# JTAG_Trace.net
KiCad netlist of a schematic drawn in Altium Designer
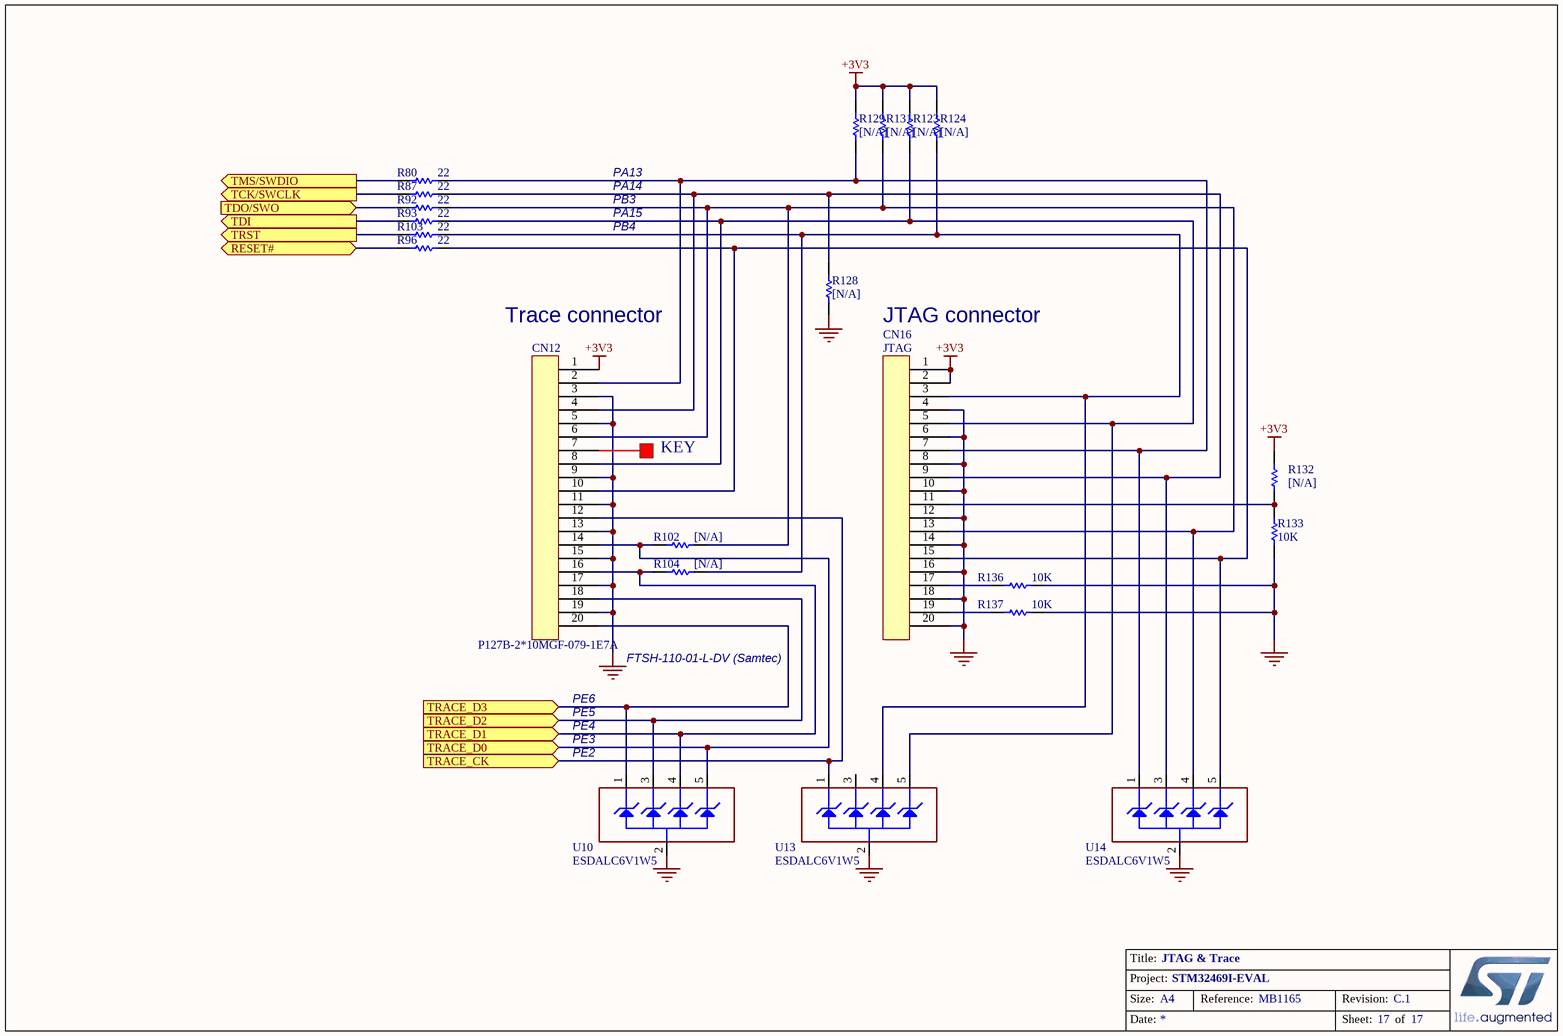
[diagram p0: JTAG&Trace.SchDoc]

(export (version "E")
  (design (tool "Eeschema 10.0.6"))
  (components
    (comp (ref "CN12")
      (value "P127B-2*10MGF-079-1E7A")
      (footprint "FTSH-110-01-L-DV")
      (libsource (lib "*") (part "20PIN1"))
    )
    (comp (ref "CN16") (value "JTAG") (footprint "IDC20S") (libsource (lib "*") (part "20PIN1")))
    (comp (ref "R80")
      (value "22")
      (footprint "0603R")
      (description "Resistor")
      (fields (field (name "PUBLISHER") "Altium Limited"))
      (libsource (lib "Miscellaneous Devices") (part "Res1"))
    )
    (comp (ref "R87")
      (value "22")
      (footprint "0603R")
      (description "Resistor")
      (fields (field (name "PUBLISHER") "Altium Limited"))
      (libsource (lib "Miscellaneous Devices") (part "Res1"))
    )
    (comp (ref "R92")
      (value "22")
      (footprint "0603R")
      (description "Resistor")
      (fields (field (name "PUBLISHER") "Altium Limited"))
      (libsource (lib "Miscellaneous Devices") (part "Res1"))
    )
    (comp (ref "R93")
      (value "22")
      (footprint "0603R")
      (description "Resistor")
      (fields (field (name "PUBLISHER") "Altium Limited"))
      (libsource (lib "Miscellaneous Devices") (part "Res1"))
    )
    (comp (ref "R96")
      (value "22")
      (footprint "0603R")
      (description "Resistor")
      (fields (field (name "PUBLISHER") "Altium Limited"))
      (libsource (lib "Miscellaneous Devices") (part "Res1"))
    )
    (comp (ref "R102")
      (value "[N/A]")
      (footprint "0603R")
      (description "Resistor")
      (fields (field (name "PUBLISHER") "Altium Limited"))
      (libsource (lib "Miscellaneous Devices") (part "Res1"))
    )
    (comp (ref "R103")
      (value "22")
      (footprint "0603R")
      (description "Resistor")
      (fields (field (name "PUBLISHER") "Altium Limited"))
      (libsource (lib "Miscellaneous Devices") (part "Res1"))
    )
    (comp (ref "R104")
      (value "[N/A]")
      (footprint "0603R")
      (description "Resistor")
      (fields (field (name "PUBLISHER") "Altium Limited"))
      (libsource (lib "Miscellaneous Devices") (part "Res1"))
    )
    (comp (ref "R123")
      (value "[N/A]")
      (footprint "0603R")
      (description "Resistor")
      (fields (field (name "PUBLISHER") "Altium Limited"))
      (libsource (lib "Miscellaneous Devices") (part "Res1"))
    )
    (comp (ref "R124")
      (value "[N/A]")
      (footprint "0603R")
      (description "Resistor")
      (fields (field (name "PUBLISHER") "Altium Limited"))
      (libsource (lib "Miscellaneous Devices") (part "Res1"))
    )
    (comp (ref "R128")
      (value "[N/A]")
      (footprint "0603R")
      (description "Resistor")
      (fields (field (name "PUBLISHER") "Altium Limited"))
      (libsource (lib "Miscellaneous Devices") (part "Res1"))
    )
    (comp (ref "R129")
      (value "[N/A]")
      (footprint "0603R")
      (description "Resistor")
      (fields (field (name "PUBLISHER") "Altium Limited"))
      (libsource (lib "Miscellaneous Devices") (part "Res1"))
    )
    (comp (ref "R131")
      (value "[N/A]")
      (footprint "0603R")
      (description "Resistor")
      (fields (field (name "PUBLISHER") "Altium Limited"))
      (libsource (lib "Miscellaneous Devices") (part "Res1"))
    )
    (comp (ref "R132")
      (value "[N/A]")
      (footprint "0603R")
      (description "Resistor")
      (fields (field (name "PUBLISHER") "Altium Limited"))
      (libsource (lib "Miscellaneous Devices") (part "Res1"))
    )
    (comp (ref "R133")
      (value "10K")
      (footprint "0603R")
      (description "Resistor")
      (fields (field (name "PUBLISHER") "Altium Limited"))
      (libsource (lib "Miscellaneous Devices") (part "Res1"))
    )
    (comp (ref "R136")
      (value "10K")
      (footprint "0603R")
      (description "Resistor")
      (fields (field (name "PUBLISHER") "Altium Limited"))
      (libsource (lib "Miscellaneous Devices") (part "Res1"))
    )
    (comp (ref "R137")
      (value "10K")
      (footprint "0603R")
      (description "Resistor")
      (fields (field (name "PUBLISHER") "Altium Limited"))
      (libsource (lib "Miscellaneous Devices") (part "Res1"))
    )
    (comp (ref "U10")
      (value "ESDALC6V1W5")
      (footprint "SOT-353")
      (description "Dual Transil array for ESD protection")
      (libsource (lib "MB1167_1") (part "ESDALC6V1W5"))
    )
    (comp (ref "U13")
      (value "ESDALC6V1W5")
      (footprint "SOT-353")
      (description "Dual Transil array for ESD protection")
      (libsource (lib "MB1167_1") (part "ESDALC6V1W5"))
    )
    (comp (ref "U14")
      (value "ESDALC6V1W5")
      (footprint "SOT-353")
      (description "Dual Transil array for ESD protection")
      (libsource (lib "MB1167_1") (part "ESDALC6V1W5"))
    )
  )
  (nets
    (net (code "1") (name "+3V3") (class "Default")
      (node (ref "CN12") (pin "1") (pintype "passive"))
      (node (ref "CN16") (pin "1") (pintype "passive"))
      (node (ref "CN16") (pin "2") (pintype "passive"))
      (node (ref "R123") (pin "2") (pinfunction "2_2") (pintype "passive"))
      (node (ref "R124") (pin "2") (pinfunction "2_2") (pintype "passive"))
      (node (ref "R129") (pin "2") (pinfunction "2_2") (pintype "passive"))
      (node (ref "R131") (pin "2") (pinfunction "2_2") (pintype "passive"))
      (node (ref "R132") (pin "2") (pinfunction "2_2") (pintype "passive"))
    )
    (net (code "2") (name "/RESET#") (class "Default")
      (node (ref "R96") (pin "2") (pinfunction "2_2") (pintype "passive"))
    )
    (net (code "3") (name "/TCK{slash}SWCLK") (class "Default")
      (node (ref "R87") (pin "2") (pinfunction "2_2") (pintype "passive"))
    )
    (net (code "4") (name "/TDI") (class "Default")
      (node (ref "R93") (pin "2") (pinfunction "2_2") (pintype "passive"))
    )
    (net (code "5") (name "/TDO{slash}SWO") (class "Default")
      (node (ref "R92") (pin "2") (pinfunction "2_2") (pintype "passive"))
    )
    (net (code "6") (name "/TMS{slash}SWDIO") (class "Default")
      (node (ref "R80") (pin "2") (pinfunction "2_2") (pintype "passive"))
    )
    (net (code "7") (name "/TRACE_CK") (class "Default")
      (node (ref "CN12") (pin "12") (pintype "passive"))
      (node (ref "U13") (pin "1") (pinfunction "IO1_1") (pintype "passive"))
    )
    (net (code "8") (name "/TRACE_D0") (class "Default")
      (node (ref "CN12") (pin "14") (pintype "passive"))
      (node (ref "R102") (pin "1") (pinfunction "1_1") (pintype "passive"))
      (node (ref "U10") (pin "5") (pinfunction "IO4_5") (pintype "passive"))
    )
    (net (code "9") (name "/TRACE_D1") (class "Default")
      (node (ref "CN12") (pin "16") (pintype "passive"))
      (node (ref "R104") (pin "1") (pinfunction "1_1") (pintype "passive"))
      (node (ref "U10") (pin "4") (pinfunction "IO3_4") (pintype "passive"))
    )
    (net (code "10") (name "/TRACE_D2") (class "Default")
      (node (ref "CN12") (pin "18") (pintype "passive"))
      (node (ref "U10") (pin "3") (pinfunction "IO2_3") (pintype "passive"))
    )
    (net (code "11") (name "/TRACE_D3") (class "Default")
      (node (ref "CN12") (pin "20") (pintype "passive"))
      (node (ref "U10") (pin "1") (pinfunction "IO1_1") (pintype "passive"))
    )
    (net (code "12") (name "/TRST") (class "Default")
      (node (ref "R103") (pin "2") (pinfunction "2_2") (pintype "passive"))
    )
    (net (code "13") (name "GND") (class "Default")
      (node (ref "CN12") (pin "11") (pintype "passive"))
      (node (ref "CN12") (pin "13") (pintype "passive"))
      (node (ref "CN12") (pin "15") (pintype "passive"))
      (node (ref "CN12") (pin "17") (pintype "passive"))
      (node (ref "CN12") (pin "19") (pintype "passive"))
      (node (ref "CN12") (pin "3") (pintype "passive"))
      (node (ref "CN12") (pin "5") (pintype "passive"))
      (node (ref "CN12") (pin "9") (pintype "passive"))
      (node (ref "CN16") (pin "10") (pintype "passive"))
      (node (ref "CN16") (pin "12") (pintype "passive"))
      (node (ref "CN16") (pin "14") (pintype "passive"))
      (node (ref "CN16") (pin "16") (pintype "passive"))
      (node (ref "CN16") (pin "18") (pintype "passive"))
      (node (ref "CN16") (pin "20") (pintype "passive"))
      (node (ref "CN16") (pin "4") (pintype "passive"))
      (node (ref "CN16") (pin "6") (pintype "passive"))
      (node (ref "CN16") (pin "8") (pintype "passive"))
      (node (ref "R128") (pin "1") (pinfunction "1_1") (pintype "passive"))
      (node (ref "R133") (pin "1") (pinfunction "1_1") (pintype "passive"))
      (node (ref "R136") (pin "1") (pinfunction "1_1") (pintype "passive"))
      (node (ref "R137") (pin "1") (pinfunction "1_1") (pintype "passive"))
      (node (ref "U10") (pin "2") (pinfunction "GND_2") (pintype "passive"))
      (node (ref "U13") (pin "2") (pinfunction "GND_2") (pintype "passive"))
      (node (ref "U14") (pin "2") (pinfunction "GND_2") (pintype "passive"))
    )
    (net (code "14") (name "Net-(CN16-Pad11)") (class "Default")
      (node (ref "CN16") (pin "11") (pintype "passive"))
      (node (ref "R132") (pin "1") (pinfunction "1_1") (pintype "passive"))
      (node (ref "R133") (pin "2") (pinfunction "2_2") (pintype "passive"))
    )
    (net (code "15") (name "Net-(CN16-Pad17)") (class "Default")
      (node (ref "CN16") (pin "17") (pintype "passive"))
      (node (ref "R136") (pin "2") (pinfunction "2_2") (pintype "passive"))
    )
    (net (code "16") (name "Net-(CN16-Pad19)") (class "Default")
      (node (ref "CN16") (pin "19") (pintype "passive"))
      (node (ref "R137") (pin "2") (pinfunction "2_2") (pintype "passive"))
    )
    (net (code "17") (name "Net-(U13-IO3)") (class "Default")
      (node (ref "CN16") (pin "3") (pintype "passive"))
      (node (ref "R103") (pin "1") (pinfunction "1_1") (pintype "passive"))
      (node (ref "R104") (pin "2") (pinfunction "2_2") (pintype "passive"))
      (node (ref "R124") (pin "1") (pinfunction "1_1") (pintype "passive"))
      (node (ref "U13") (pin "4") (pinfunction "IO3_4") (pintype "passive"))
    )
    (net (code "18") (name "Net-(U13-IO4)") (class "Default")
      (node (ref "CN12") (pin "8") (pintype "passive"))
      (node (ref "CN16") (pin "5") (pintype "passive"))
      (node (ref "R123") (pin "1") (pinfunction "1_1") (pintype "passive"))
      (node (ref "R93") (pin "1") (pinfunction "1_1") (pintype "passive"))
      (node (ref "U13") (pin "5") (pinfunction "IO4_5") (pintype "passive"))
    )
    (net (code "19") (name "Net-(U14-IO1)") (class "Default")
      (node (ref "CN12") (pin "2") (pintype "passive"))
      (node (ref "CN16") (pin "7") (pintype "passive"))
      (node (ref "R129") (pin "1") (pinfunction "1_1") (pintype "passive"))
      (node (ref "R80") (pin "1") (pinfunction "1_1") (pintype "passive"))
      (node (ref "U14") (pin "1") (pinfunction "IO1_1") (pintype "passive"))
    )
    (net (code "20") (name "Net-(U14-IO2)") (class "Default")
      (node (ref "CN12") (pin "4") (pintype "passive"))
      (node (ref "CN16") (pin "9") (pintype "passive"))
      (node (ref "R128") (pin "2") (pinfunction "2_2") (pintype "passive"))
      (node (ref "R87") (pin "1") (pinfunction "1_1") (pintype "passive"))
      (node (ref "U14") (pin "3") (pinfunction "IO2_3") (pintype "passive"))
    )
    (net (code "21") (name "Net-(U14-IO3)") (class "Default")
      (node (ref "CN12") (pin "6") (pintype "passive"))
      (node (ref "CN16") (pin "13") (pintype "passive"))
      (node (ref "R102") (pin "2") (pinfunction "2_2") (pintype "passive"))
      (node (ref "R131") (pin "1") (pinfunction "1_1") (pintype "passive"))
      (node (ref "R92") (pin "1") (pinfunction "1_1") (pintype "passive"))
      (node (ref "U14") (pin "4") (pinfunction "IO3_4") (pintype "passive"))
    )
    (net (code "22") (name "Net-(U14-IO4)") (class "Default")
      (node (ref "CN12") (pin "10") (pintype "passive"))
      (node (ref "CN16") (pin "15") (pintype "passive"))
      (node (ref "R96") (pin "1") (pinfunction "1_1") (pintype "passive"))
      (node (ref "U14") (pin "5") (pinfunction "IO4_5") (pintype "passive"))
    )
    (net (code "23") (name "unconnected-(CN12-Pad7)") (class "Default")
      (node (ref "CN12") (pin "7") (pintype "passive"))
    )
    (net (code "24") (name "unconnected-(U13-IO2-Pad3)") (class "Default")
      (node (ref "U13") (pin "3") (pinfunction "IO2_3") (pintype "passive"))
    )
  )
)
